# Regelaar.net
KiCad netlist of a schematic drawn in Altium Designer
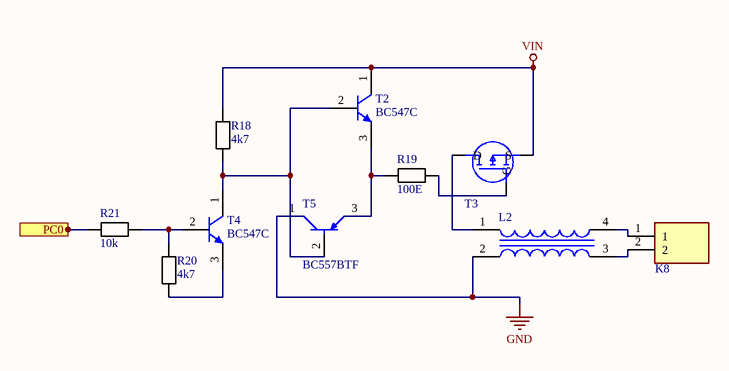
[diagram p0: Regelaar.SchDoc]

(export (version "E")
  (design (tool "Eeschema 10.0.6"))
  (components
    (comp (ref "K8")
      (value "282836-2")
      (footprint "Schroefconnector 2 Pin - duplicate")
      (description "Connector")
      (libsource (lib "schoolprojectcomponentlib") (part "Schroefconnector 2 Pin R"))
    )
    (comp (ref "L2")
      (value "Smoorspoel commom mode")
      (footprint "Common mode smoorspoel")
      (description "Transformer CM2545X171B-10")
      (fields (field (name "MANUFACTURER_PART_NUMBER") "CM2545X171B-10"))
      (libsource (lib "schoolprojectcomponentlib") (part "Smoorspoel commom mode"))
    )
    (comp (ref "R18")
      (value "4k7")
      (footprint "weerstand")
      (fields (field (name "MANUFACTURER") "Vishay Dale") (field (name "PART NUMBER") "CRCW08050000Z0EA"))
      (libsource (lib "schoolprojectcomponentlib") (part "weerstand"))
    )
    (comp (ref "R19")
      (value "100E")
      (footprint "weerstand")
      (fields (field (name "MANUFACTURER") "Vishay Dale") (field (name "PART NUMBER") "CRCW08050000Z0EA"))
      (libsource (lib "schoolprojectcomponentlib") (part "weerstand"))
    )
    (comp (ref "R20")
      (value "4k7")
      (footprint "weerstand")
      (fields (field (name "MANUFACTURER") "Vishay Dale") (field (name "PART NUMBER") "CRCW08050000Z0EA"))
      (libsource (lib "schoolprojectcomponentlib") (part "weerstand"))
    )
    (comp (ref "R21")
      (value "10k")
      (footprint "weerstand")
      (fields (field (name "MANUFACTURER") "Vishay Dale") (field (name "PART NUMBER") "CRCW08050000Z0EA"))
      (libsource (lib "schoolprojectcomponentlib") (part "weerstand"))
    )
    (comp (ref "T2")
      (value "BC547C")
      (footprint "BC547C (transistor)")
      (description "Amplifier Transistor, NPN Silicon, 3-Pin, 0,1A TO-92, Bulk Box")
      (fields (field (name "MANUFACTURER") "On Semiconductor"))
      (libsource (lib "schoolprojectcomponentlib") (part "BC547C"))
    )
    (comp (ref "T3")
      (value "IRF9Z34NPBF")
      (footprint "MOSFET")
      (description "MOSFET (P-Channel)")
      (fields (field (name "MOUSER2 PART NUMBER") "942-IRF9Z34NPBF"))
      (libsource (lib "schoolprojectcomponentlib") (part "MOSFET"))
    )
    (comp (ref "T4")
      (value "BC547C")
      (footprint "BC547C (transistor)")
      (description "Amplifier Transistor, NPN Silicon, 3-Pin, 0,1A TO-92, Bulk Box")
      (fields (field (name "MANUFACTURER") "On Semiconductor"))
      (libsource (lib "schoolprojectcomponentlib") (part "BC547C"))
    )
    (comp (ref "T5")
      (value "BC557BTF")
      (footprint "transistor BC557")
      (description "BC557BTF Small Signal Bipolar Transistor, 0.1A I(C), 45V V(BR)CEO, 1-Element, PNP, Silicon, TO-92")
      (libsource (lib "schoolprojectcomponentlib") (part "BC557"))
    )
  )
  (nets
    (net (code "1") (name "/PC0") (class "Default")
      (node (ref "R21") (pin "1") (pinfunction "1_1") (pintype "passive"))
    )
    (net (code "2") (name "GND") (class "Default")
      (node (ref "L2") (pin "2") (pinfunction "SEC+_2") (pintype "passive"))
      (node (ref "T5") (pin "1") (pinfunction "C_1") (pintype "passive"))
    )
    (net (code "3") (name "Net-(L2-PRI+)") (class "Default")
      (node (ref "L2") (pin "1") (pinfunction "PRI+_1") (pintype "passive"))
      (node (ref "T3") (pin "3") (pinfunction "D_3") (pintype "passive"))
    )
    (net (code "4") (name "Net-(L2-PRI-)") (class "Default")
      (node (ref "K8") (pin "1") (pinfunction "1_1") (pintype "passive"))
      (node (ref "L2") (pin "4") (pinfunction "PRI-_4") (pintype "passive"))
    )
    (net (code "5") (name "Net-(L2-SEC-)") (class "Default")
      (node (ref "K8") (pin "2") (pinfunction "2_2") (pintype "passive"))
      (node (ref "L2") (pin "3") (pinfunction "SEC-_3") (pintype "passive"))
    )
    (net (code "6") (name "Net-(T2-B)") (class "Default")
      (node (ref "R18") (pin "1") (pinfunction "1_1") (pintype "passive"))
      (node (ref "T2") (pin "2") (pinfunction "B_2") (pintype "passive"))
      (node (ref "T4") (pin "1") (pinfunction "C_1") (pintype "passive"))
      (node (ref "T5") (pin "2") (pinfunction "B_2") (pintype "passive"))
    )
    (net (code "7") (name "Net-(T2-E)") (class "Default")
      (node (ref "R19") (pin "1") (pinfunction "1_1") (pintype "passive"))
      (node (ref "T2") (pin "3") (pinfunction "E_3") (pintype "passive"))
      (node (ref "T5") (pin "3") (pintype "passive"))
    )
    (net (code "8") (name "Net-(T3-G)") (class "Default")
      (node (ref "R19") (pin "2") (pinfunction "2_2") (pintype "passive"))
      (node (ref "T3") (pin "1") (pinfunction "G_1") (pintype "passive"))
    )
    (net (code "9") (name "Net-(T4-B)") (class "Default")
      (node (ref "R20") (pin "2") (pinfunction "2_2") (pintype "passive"))
      (node (ref "R21") (pin "2") (pinfunction "2_2") (pintype "passive"))
      (node (ref "T4") (pin "2") (pinfunction "B_2") (pintype "passive"))
    )
    (net (code "10") (name "Net-(T4-E)") (class "Default")
      (node (ref "R20") (pin "1") (pinfunction "1_1") (pintype "passive"))
      (node (ref "T4") (pin "3") (pinfunction "E_3") (pintype "passive"))
    )
    (net (code "11") (name "VIN") (class "Default")
      (node (ref "R18") (pin "2") (pinfunction "2_2") (pintype "passive"))
      (node (ref "T2") (pin "1") (pinfunction "C_1") (pintype "passive"))
      (node (ref "T3") (pin "2") (pinfunction "S_2") (pintype "passive"))
    )
  )
)
